# Sheet.net
KiCad netlist of a schematic drawn in Altium Designer
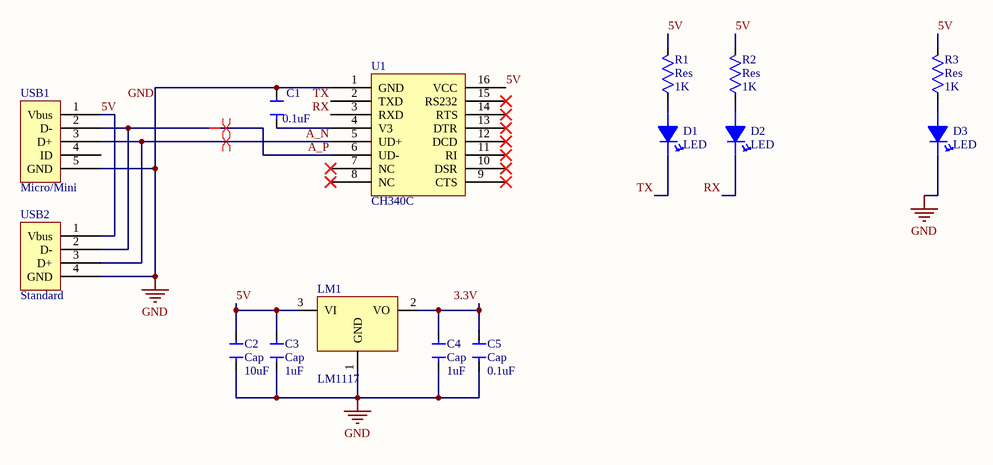
[diagram p0: Sheet.SchDoc]

(export (version "E")
  (design (tool "Eeschema 10.0.6"))
  (components
    (comp (ref "C1")
      (value "0.1uF")
      (footprint "Cap_0603")
      (fields (field (name "Comment") "Cap"))
      (libsource (lib "ZGR") (part "Cap"))
    )
    (comp (ref "C2")
      (value "Cap")
      (footprint "Cap_0603")
      (fields (field (name "ALTIUM_VALUE") "10uF"))
      (libsource (lib "ZGR") (part "Cap"))
    )
    (comp (ref "C3")
      (value "Cap")
      (footprint "Cap_0603")
      (fields (field (name "ALTIUM_VALUE") "1uF"))
      (libsource (lib "ZGR") (part "Cap"))
    )
    (comp (ref "C4")
      (value "Cap")
      (footprint "Cap_0603")
      (fields (field (name "ALTIUM_VALUE") "1uF"))
      (libsource (lib "ZGR") (part "Cap"))
    )
    (comp (ref "C5")
      (value "Cap")
      (footprint "Cap_0603")
      (fields (field (name "ALTIUM_VALUE") "0.1uF"))
      (libsource (lib "ZGR") (part "Cap"))
    )
    (comp (ref "D1") (value "LED") (footprint "SMD-0603_LED") (libsource (lib "ZGR") (part "LED")))
    (comp (ref "D2") (value "LED") (footprint "SMD-0603_LED") (libsource (lib "ZGR") (part "LED")))
    (comp (ref "D3") (value "LED") (footprint "SMD-0603_LED") (libsource (lib "ZGR") (part "LED")))
    (comp (ref "LM1") (value "LM1117") (footprint "SOT-223") (libsource (lib "ZGR") (part "LM1117")))
    (comp (ref "R1")
      (value "Res")
      (footprint "RES_0603")
      (fields (field (name "ALTIUM_VALUE") "1K"))
      (libsource (lib "ZGR") (part "Res"))
    )
    (comp (ref "R2")
      (value "Res")
      (footprint "RES_0603")
      (fields (field (name "ALTIUM_VALUE") "1K"))
      (libsource (lib "ZGR") (part "Res"))
    )
    (comp (ref "R3")
      (value "Res")
      (footprint "RES_0603")
      (fields (field (name "ALTIUM_VALUE") "1K"))
      (libsource (lib "ZGR") (part "Res"))
    )
    (comp (ref "U1")
      (value "CH340C")
      (footprint "SOP127P600X265-16N")
      (libsource (lib "ZGR") (part "CH340C"))
    )
    (comp (ref "USB1")
      (value "Micro/Mini")
      (footprint "USB_Mini-B_S_SMT")
      (libsource (lib "ZGR") (part "USB2"))
    )
    (comp (ref "USB2")
      (value "Standard")
      (footprint "USB_Type-A_P_Thru-Hole")
      (libsource (lib "ZGR") (part "USB1"))
    )
  )
  (nets
    (net (code "1") (name "/3.3V") (class "Default")
      (node (ref "C4") (pin "1") (pinfunction "1_1") (pintype "passive"))
      (node (ref "C5") (pin "1") (pinfunction "1_1") (pintype "passive"))
      (node (ref "LM1") (pin "2") (pinfunction "VO_2") (pintype "passive"))
    )
    (net (code "2") (name "/5V") (class "Default")
      (node (ref "C2") (pin "1") (pinfunction "1_1") (pintype "passive"))
      (node (ref "C3") (pin "1") (pinfunction "1_1") (pintype "passive"))
      (node (ref "LM1") (pin "3") (pinfunction "VI_3") (pintype "passive"))
      (node (ref "R1") (pin "1") (pinfunction "1_1") (pintype "passive"))
      (node (ref "R2") (pin "1") (pinfunction "1_1") (pintype "passive"))
      (node (ref "R3") (pin "1") (pinfunction "1_1") (pintype "passive"))
      (node (ref "U1") (pin "16") (pinfunction "VCC_16") (pintype "passive"))
      (node (ref "USB1") (pin "1") (pinfunction "Vbus_1") (pintype "passive"))
      (node (ref "USB2") (pin "1") (pinfunction "Vbus_1") (pintype "passive"))
    )
    (net (code "3") (name "/A_N") (class "Default")
      (node (ref "U1") (pin "5") (pinfunction "UD+_5") (pintype "passive"))
      (node (ref "USB1") (pin "3") (pinfunction "D+_3") (pintype "passive"))
      (node (ref "USB2") (pin "3") (pinfunction "D+_3") (pintype "passive"))
    )
    (net (code "4") (name "/A_P") (class "Default")
      (node (ref "U1") (pin "6") (pinfunction "UD-_6") (pintype "passive"))
      (node (ref "USB1") (pin "2") (pinfunction "D-_2") (pintype "passive"))
      (node (ref "USB2") (pin "2") (pinfunction "D-_2") (pintype "passive"))
    )
    (net (code "5") (name "/RX") (class "Default")
      (node (ref "D2") (pin "2") (pinfunction "2_2") (pintype "passive"))
      (node (ref "U1") (pin "3") (pinfunction "RXD_3") (pintype "passive"))
    )
    (net (code "6") (name "/TX") (class "Default")
      (node (ref "D1") (pin "2") (pinfunction "2_2") (pintype "passive"))
      (node (ref "U1") (pin "2") (pinfunction "TXD_2") (pintype "passive"))
    )
    (net (code "7") (name "GND") (class "Default")
      (node (ref "C1") (pin "1") (pinfunction "1_1") (pintype "passive"))
      (node (ref "C2") (pin "2") (pinfunction "2_2") (pintype "passive"))
      (node (ref "C3") (pin "2") (pinfunction "2_2") (pintype "passive"))
      (node (ref "C4") (pin "2") (pinfunction "2_2") (pintype "passive"))
      (node (ref "C5") (pin "2") (pinfunction "2_2") (pintype "passive"))
      (node (ref "D3") (pin "2") (pinfunction "2_2") (pintype "passive"))
      (node (ref "LM1") (pin "1") (pinfunction "GND_1") (pintype "passive"))
      (node (ref "U1") (pin "1") (pinfunction "GND_1") (pintype "passive"))
      (node (ref "USB1") (pin "5") (pinfunction "GND_5") (pintype "passive"))
      (node (ref "USB2") (pin "4") (pinfunction "GND_4") (pintype "passive"))
    )
    (net (code "8") (name "Net-(D1-Pad1)") (class "Default")
      (node (ref "D1") (pin "1") (pinfunction "1_1") (pintype "passive"))
      (node (ref "R1") (pin "2") (pinfunction "2_2") (pintype "passive"))
    )
    (net (code "9") (name "Net-(D2-Pad1)") (class "Default")
      (node (ref "D2") (pin "1") (pinfunction "1_1") (pintype "passive"))
      (node (ref "R2") (pin "2") (pinfunction "2_2") (pintype "passive"))
    )
    (net (code "10") (name "Net-(D3-Pad1)") (class "Default")
      (node (ref "D3") (pin "1") (pinfunction "1_1") (pintype "passive"))
      (node (ref "R3") (pin "2") (pinfunction "2_2") (pintype "passive"))
    )
    (net (code "11") (name "Net-(U1-V3)") (class "Default")
      (node (ref "C1") (pin "2") (pinfunction "2_2") (pintype "passive"))
      (node (ref "U1") (pin "4") (pinfunction "V3_4") (pintype "passive"))
    )
    (net (code "12") (name "unconnected-(U1-CTS-Pad9)") (class "Default")
      (node (ref "U1") (pin "9") (pinfunction "CTS_9") (pintype "passive+no_connect"))
    )
    (net (code "13") (name "unconnected-(U1-DCD-Pad12)") (class "Default")
      (node (ref "U1") (pin "12") (pinfunction "DCD_12") (pintype "passive+no_connect"))
    )
    (net (code "14") (name "unconnected-(U1-DSR-Pad10)") (class "Default")
      (node (ref "U1") (pin "10") (pinfunction "DSR_10") (pintype "passive+no_connect"))
    )
    (net (code "15") (name "unconnected-(U1-DTR-Pad13)") (class "Default")
      (node (ref "U1") (pin "13") (pinfunction "DTR_13") (pintype "passive+no_connect"))
    )
    (net (code "16") (name "unconnected-(U1-NC-Pad7)") (class "Default")
      (node (ref "U1") (pin "7") (pinfunction "NC_7") (pintype "passive+no_connect"))
    )
    (net (code "17") (name "unconnected-(U1-NC-Pad8)") (class "Default")
      (node (ref "U1") (pin "8") (pinfunction "NC_8") (pintype "passive+no_connect"))
    )
    (net (code "18") (name "unconnected-(U1-RI-Pad11)") (class "Default")
      (node (ref "U1") (pin "11") (pinfunction "RI_11") (pintype "passive+no_connect"))
    )
    (net (code "19") (name "unconnected-(U1-RS232-Pad15)") (class "Default")
      (node (ref "U1") (pin "15") (pinfunction "RS232_15") (pintype "passive+no_connect"))
    )
    (net (code "20") (name "unconnected-(U1-RTS-Pad14)") (class "Default")
      (node (ref "U1") (pin "14") (pinfunction "RTS_14") (pintype "passive+no_connect"))
    )
    (net (code "21") (name "unconnected-(USB1-ID-Pad4)") (class "Default")
      (node (ref "USB1") (pin "4") (pinfunction "ID_4") (pintype "passive"))
    )
  )
)
